# FPGA.net
KiCad netlist of a schematic drawn in Altium Designer
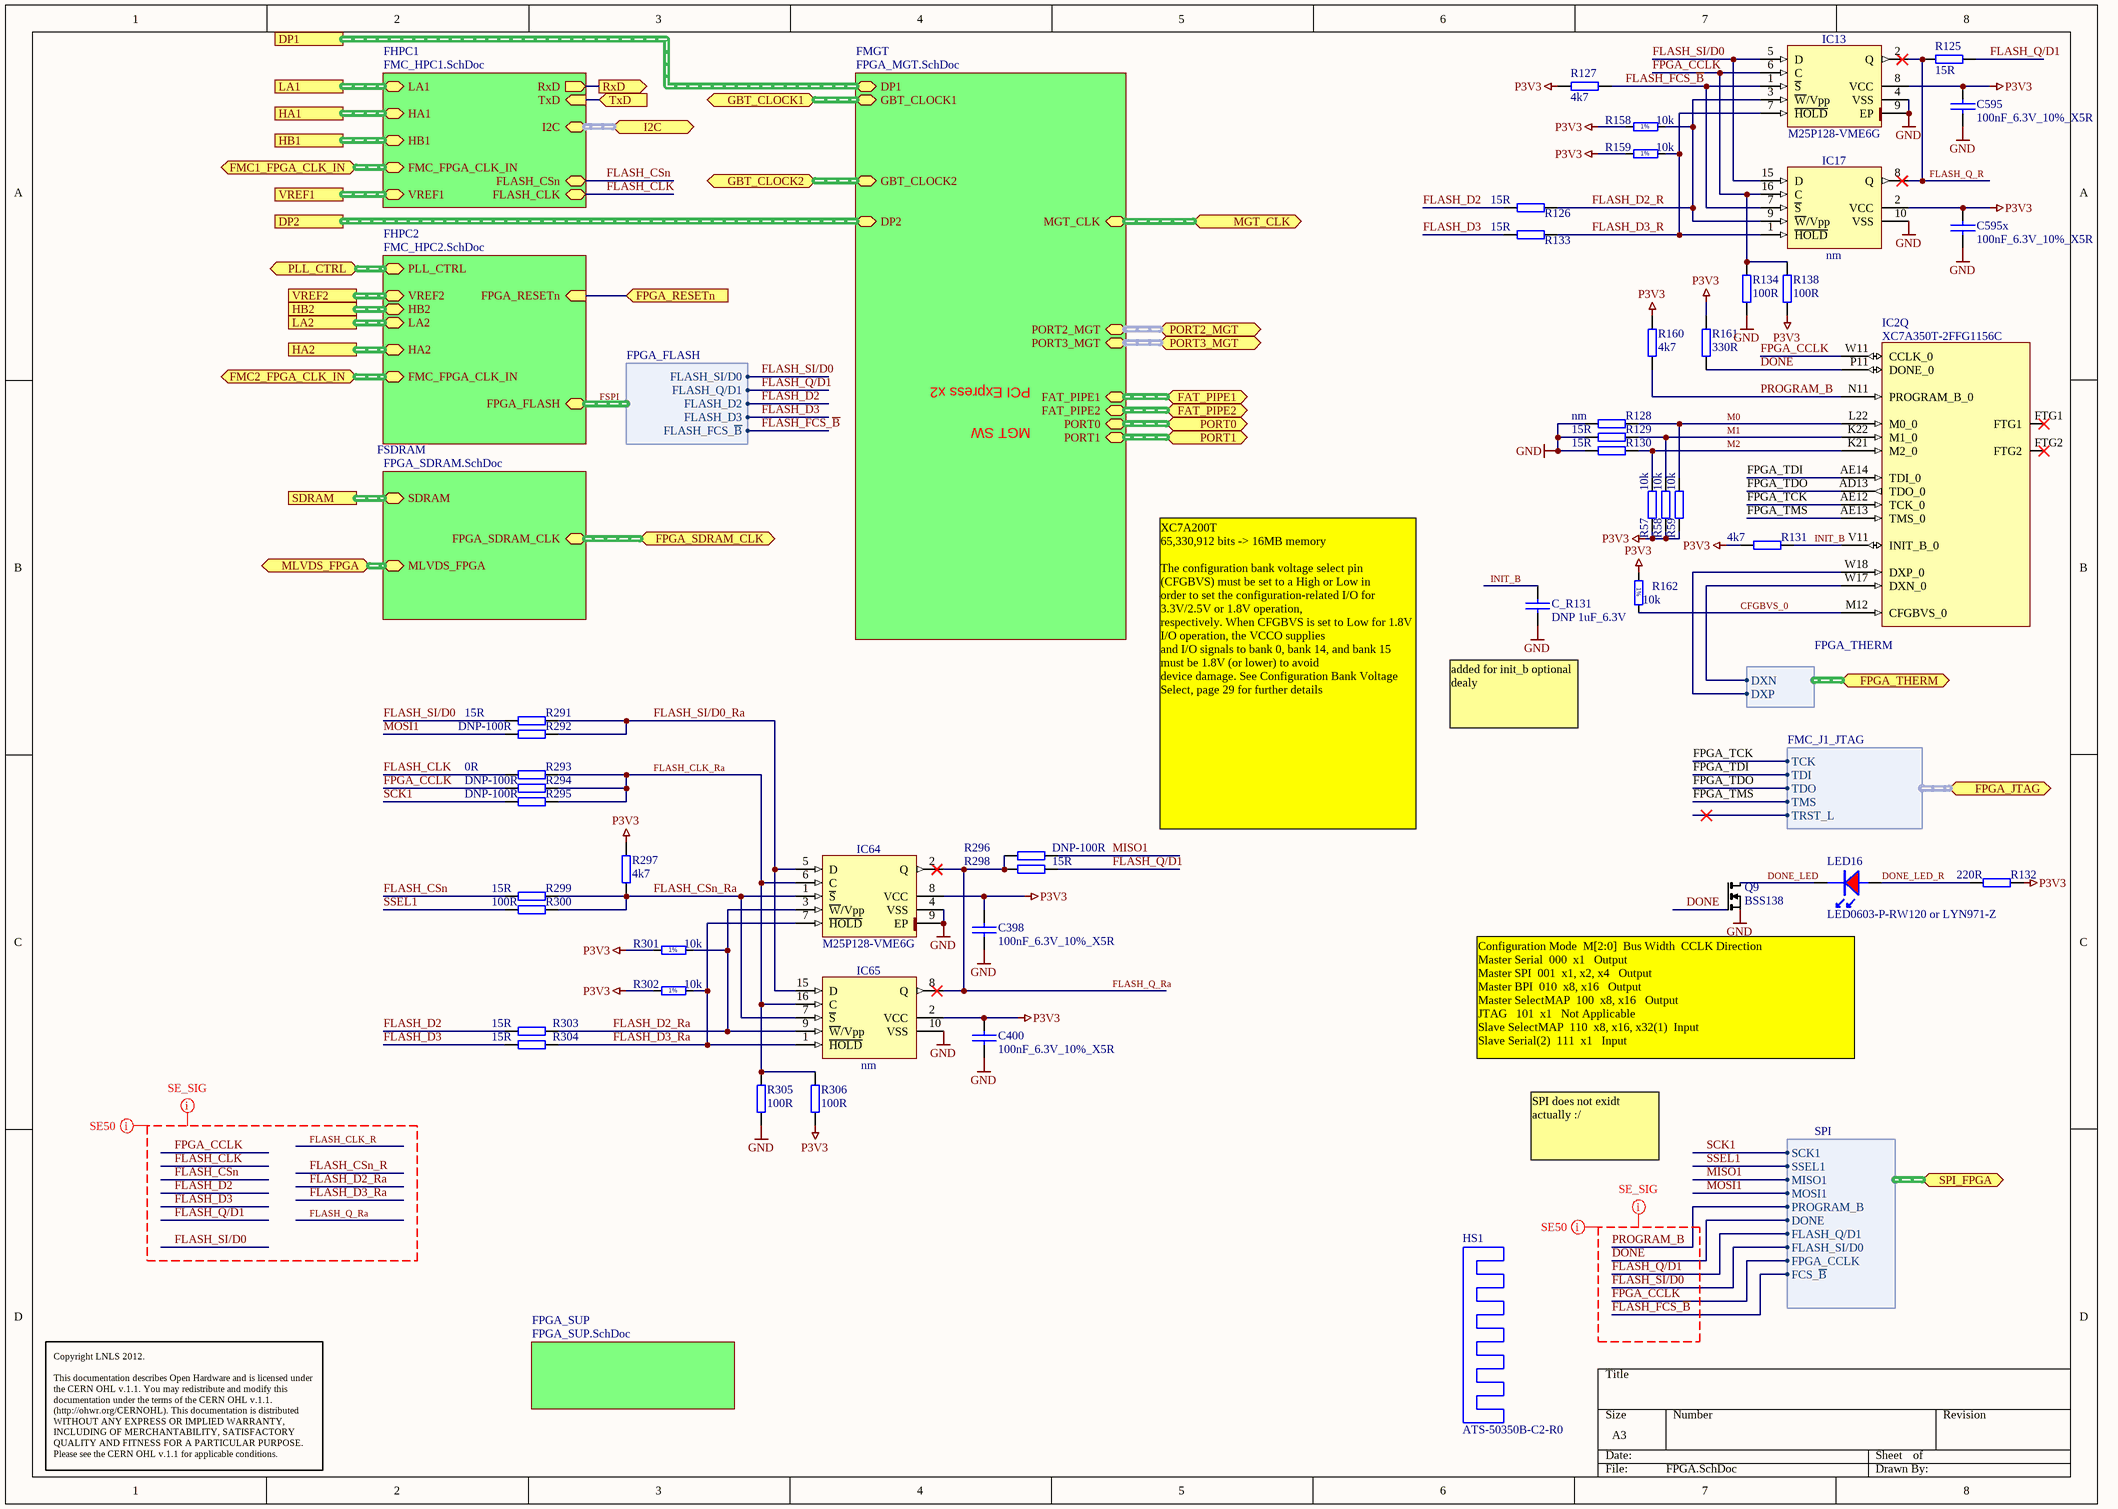
[diagram p0: FPGA.SchDoc]

(export (version "E")
  (design (tool "Eeschema 10.0.6"))
  (components
    (comp (ref "C398")
      (value "100nF_6.3V_10%_X5R")
      (footprint "0201C")
      (description "Capacitor SMD")
      (libsource (lib "LIBRARY_SCH") (part "CAP_SMD_0201"))
    )
    (comp (ref "C400")
      (value "100nF_6.3V_10%_X5R")
      (footprint "0201C")
      (description "Capacitor SMD")
      (libsource (lib "LIBRARY_SCH") (part "CAP_SMD_0201"))
    )
    (comp (ref "C595")
      (value "100nF_6.3V_10%_X5R")
      (footprint "0201C")
      (description "Capacitor SMD")
      (libsource (lib "LIBRARY_SCH") (part "CAP_SMD_0201"))
    )
    (comp (ref "C595x")
      (value "100nF_6.3V_10%_X5R")
      (footprint "0201C")
      (description "Capacitor SMD")
      (libsource (lib "LIBRARY_SCH") (part "CAP_SMD_0201"))
    )
    (comp (ref "C_R131")
      (value "DNP 1uF_6.3V")
      (footprint "0603C")
      (description "Capacitor SMD")
      (libsource (lib "LIBRARY_SCH") (part "CAP_SMD_0603"))
    )
    (comp (ref "HS1")
      (value "ATS-50350B-C2-R0")
      (footprint "HEAT_SINK_ATS-50350B-C2-R0")
      (description "Heat sink BGA 35x35(44.9)mm")
      (libsource (lib "LIBRARY_SCH") (part "HEAT_SINK_ATS-50350B-C2-R0"))
    )
    (comp (ref "IC2")
      (value "XC7A350T-2FFG1156C")
      (footprint "BGA1156C100P34X34_3500X3500X335")
      (description "Artix-6 FPGA, 16 GTPs, 600 User I/Os, 1156-Pin BGA, Speed Grade 2, Commercial Grade, Pb-Free")
      (fields (field (name "MANUFACTURER") "XILINX") (field (name "AUTHOR") "CERN DEM JLC"))
      (libsource (lib "AMC_FMC_Carrier") (part "XC7A350T-2FFG1156C"))
    )
    (comp (ref "IC13")
      (value "M25P128-VME6G")
      (footprint "PSON127P800X600X100-9N-R640X480")
      (description "128 Mbit (Multilevel), low-voltage, Serial Flash memory with 50-MHz SPI bus interface")
      (fields (field (name "MANUFACTURER") "NUMONYX") (field (name "AUTHOR") "CERN DEM JLC"))
      (libsource (lib "ICs And Semiconductors") (part "M25P128-VME"))
    )
    (comp (ref "IC17")
      (value "nm")
      (footprint "SOIC127P1030X265-16N")
      (description "128 Mbit (Multilevel), low-voltage, Serial Flash memory with 50-MHz SPI bus interface")
      (fields
        (field (name "PART NUMBER") "M25P128-VMF6G")
        (field (name "MANUFACTURER") "NUMONYX")
        (field (name "AUTHOR") "CERN DEM JLC")
      )
      (libsource (lib "ICs And Semiconductors") (part "M25P128-VMF"))
    )
    (comp (ref "IC64")
      (value "M25P128-VME6G")
      (footprint "PSON127P800X600X100-9N-R640X480")
      (description "128 Mbit (Multilevel), low-voltage, Serial Flash memory with 50-MHz SPI bus interface")
      (fields (field (name "MANUFACTURER") "NUMONYX") (field (name "AUTHOR") "CERN DEM JLC"))
      (libsource (lib "ICs And Semiconductors") (part "M25P128-VME"))
    )
    (comp (ref "IC65")
      (value "nm")
      (footprint "SOIC127P1030X265-16N")
      (description "128 Mbit (Multilevel), low-voltage, Serial Flash memory with 50-MHz SPI bus interface")
      (fields
        (field (name "PART NUMBER") "M25P128-VMF6G")
        (field (name "MANUFACTURER") "NUMONYX")
        (field (name "AUTHOR") "CERN DEM JLC")
      )
      (libsource (lib "ICs And Semiconductors") (part "M25P128-VMF"))
    )
    (comp (ref "LED16")
      (value "LED0603-P-RW120 or LYN971-Z")
      (footprint "led_0603R")
      (description "LED 0603 red")
      (libsource (lib "LIBRARY_SCH") (part "LED_0603R"))
    )
    (comp (ref "Q9") (value "BSS138") (footprint "SOT-23") (libsource (lib "LIBRARY_SCH") (part "Q_BSS138")))
    (comp (ref "R57")
      (value "10k")
      (footprint "0402R")
      (description "SMD Resistor")
      (libsource (lib "LIBRARY_SCH") (part "RES_0402"))
    )
    (comp (ref "R58")
      (value "10k")
      (footprint "0402R")
      (description "SMD Resistor")
      (libsource (lib "LIBRARY_SCH") (part "RES_0402"))
    )
    (comp (ref "R59")
      (value "10k")
      (footprint "0402R")
      (description "SMD Resistor")
      (libsource (lib "LIBRARY_SCH") (part "RES_0402"))
    )
    (comp (ref "R125")
      (value "15R")
      (footprint "0402R")
      (description "SMD Resistor")
      (libsource (lib "LIBRARY_SCH") (part "RES_0402"))
    )
    (comp (ref "R126")
      (value "15R")
      (footprint "0402R")
      (description "SMD Resistor")
      (libsource (lib "LIBRARY_SCH") (part "RES_0402"))
    )
    (comp (ref "R127")
      (value "4k7")
      (footprint "0402R")
      (description "SMD Resistor")
      (libsource (lib "LIBRARY_SCH") (part "RES_0402"))
    )
    (comp (ref "R128")
      (value "nm")
      (footprint "0402R")
      (description "SMD Resistor")
      (libsource (lib "LIBRARY_SCH") (part "RES_0402"))
    )
    (comp (ref "R129")
      (value "15R")
      (footprint "0402R")
      (description "SMD Resistor")
      (libsource (lib "LIBRARY_SCH") (part "RES_0402"))
    )
    (comp (ref "R130")
      (value "15R")
      (footprint "0402R")
      (description "SMD Resistor")
      (libsource (lib "LIBRARY_SCH") (part "RES_0402"))
    )
    (comp (ref "R131")
      (value "4k7")
      (footprint "0402R")
      (description "SMD Resistor")
      (libsource (lib "LIBRARY_SCH") (part "RES_0402"))
    )
    (comp (ref "R132")
      (value "220R")
      (footprint "0402R")
      (description "SMD Resistor")
      (libsource (lib "LIBRARY_SCH") (part "RES_0402"))
    )
    (comp (ref "R133")
      (value "15R")
      (footprint "0402R")
      (description "SMD Resistor")
      (libsource (lib "LIBRARY_SCH") (part "RES_0402"))
    )
    (comp (ref "R134")
      (value "100R")
      (footprint "0402R")
      (description "SMD Resistor")
      (libsource (lib "LIBRARY_SCH") (part "RES_0402"))
    )
    (comp (ref "R138")
      (value "100R")
      (footprint "0402R")
      (description "SMD Resistor")
      (libsource (lib "LIBRARY_SCH") (part "RES_0402"))
    )
    (comp (ref "R158")
      (value "10k")
      (footprint "0402R")
      (description "Resistor - 1%")
      (fields
        (field (name "PART NUMBER") "R0603_10K_1%_0.1W_100PPM")
        (field (name "POWER") "0.1W")
        (field (name "AUTHOR") "CERN DEM JLC")
      )
      (libsource (lib "Resistors") (part "Resistor - 1%"))
    )
    (comp (ref "R159")
      (value "10k")
      (footprint "0402R")
      (description "Resistor - 1%")
      (fields
        (field (name "PART NUMBER") "R0603_10K_1%_0.1W_100PPM")
        (field (name "POWER") "0.1W")
        (field (name "AUTHOR") "CERN DEM JLC")
      )
      (libsource (lib "Resistors") (part "Resistor - 1%"))
    )
    (comp (ref "R160")
      (value "4k7")
      (footprint "0402R")
      (description "SMD Resistor")
      (libsource (lib "LIBRARY_SCH") (part "RES_0402"))
    )
    (comp (ref "R161")
      (value "330R")
      (footprint "0402R")
      (description "SMD Resistor")
      (libsource (lib "LIBRARY_SCH") (part "RES_0402"))
    )
    (comp (ref "R162")
      (value "10k")
      (footprint "0402R")
      (description "Resistor - 1%")
      (fields
        (field (name "PART NUMBER") "R0603_10K_1%_0.1W_100PPM")
        (field (name "POWER") "0.1W")
        (field (name "AUTHOR") "CERN DEM JLC")
      )
      (libsource (lib "Resistors") (part "Resistor - 1%"))
    )
    (comp (ref "R291")
      (value "15R")
      (footprint "0402R")
      (description "SMD Resistor")
      (libsource (lib "LIBRARY_SCH") (part "RES_0402"))
    )
    (comp (ref "R292")
      (value "DNP-100R")
      (footprint "0402R")
      (description "SMD Resistor")
      (libsource (lib "LIBRARY_SCH") (part "RES_0402"))
    )
    (comp (ref "R293")
      (value "0R")
      (footprint "0402R")
      (description "SMD Resistor")
      (libsource (lib "LIBRARY_SCH") (part "RES_0402"))
    )
    (comp (ref "R294")
      (value "DNP-100R")
      (footprint "0402R")
      (description "SMD Resistor")
      (libsource (lib "LIBRARY_SCH") (part "RES_0402"))
    )
    (comp (ref "R295")
      (value "DNP-100R")
      (footprint "0402R")
      (description "SMD Resistor")
      (libsource (lib "LIBRARY_SCH") (part "RES_0402"))
    )
    (comp (ref "R296")
      (value "DNP-100R")
      (footprint "0402R")
      (description "SMD Resistor")
      (libsource (lib "LIBRARY_SCH") (part "RES_0402"))
    )
    (comp (ref "R297")
      (value "4k7")
      (footprint "0402R")
      (description "SMD Resistor")
      (libsource (lib "LIBRARY_SCH") (part "RES_0402"))
    )
    (comp (ref "R298")
      (value "15R")
      (footprint "0402R")
      (description "SMD Resistor")
      (libsource (lib "LIBRARY_SCH") (part "RES_0402"))
    )
    (comp (ref "R299")
      (value "15R")
      (footprint "0402R")
      (description "SMD Resistor")
      (libsource (lib "LIBRARY_SCH") (part "RES_0402"))
    )
    (comp (ref "R300")
      (value "100R")
      (footprint "0402R")
      (description "SMD Resistor")
      (libsource (lib "LIBRARY_SCH") (part "RES_0402"))
    )
    (comp (ref "R301")
      (value "10k")
      (footprint "0402R")
      (description "Resistor - 1%")
      (fields
        (field (name "PART NUMBER") "R0603_10K_1%_0.1W_100PPM")
        (field (name "POWER") "0.1W")
        (field (name "AUTHOR") "CERN DEM JLC")
      )
      (libsource (lib "Resistors") (part "Resistor - 1%"))
    )
    (comp (ref "R302")
      (value "10k")
      (footprint "0402R")
      (description "Resistor - 1%")
      (fields
        (field (name "PART NUMBER") "R0603_10K_1%_0.1W_100PPM")
        (field (name "POWER") "0.1W")
        (field (name "AUTHOR") "CERN DEM JLC")
      )
      (libsource (lib "Resistors") (part "Resistor - 1%"))
    )
    (comp (ref "R303")
      (value "15R")
      (footprint "0402R")
      (description "SMD Resistor")
      (libsource (lib "LIBRARY_SCH") (part "RES_0402"))
    )
    (comp (ref "R304")
      (value "15R")
      (footprint "0402R")
      (description "SMD Resistor")
      (libsource (lib "LIBRARY_SCH") (part "RES_0402"))
    )
    (comp (ref "R305")
      (value "100R")
      (footprint "0402R")
      (description "SMD Resistor")
      (libsource (lib "LIBRARY_SCH") (part "RES_0402"))
    )
    (comp (ref "R306")
      (value "100R")
      (footprint "0402R")
      (description "SMD Resistor")
      (libsource (lib "LIBRARY_SCH") (part "RES_0402"))
    )
  )
  (nets
    (net (code "12") (name "/CFGBVS_0") (class "Default")
      (node (ref "IC2") (pin "M12") (pinfunction "CFGBVS_0_M12") (pintype "input"))
      (node (ref "R162") (pin "2") (pinfunction "2_2") (pintype "passive"))
    )
    (net (code "13") (name "/DONE") (class "Default")
      (node (ref "IC2") (pin "P11") (pinfunction "DONE_0_P11") (pintype "bidirectional"))
      (node (ref "Q9") (pin "1") (pinfunction "G_1") (pintype "input"))
      (node (ref "R161") (pin "1") (pinfunction "1_1") (pintype "passive"))
    )
    (net (code "14") (name "/DONE_LED") (class "Default")
      (node (ref "LED16") (pin "K") (pinfunction "K_K") (pintype "passive"))
      (node (ref "Q9") (pin "3") (pinfunction "D_3") (pintype "passive"))
    )
    (net (code "15") (name "/DONE_LED_R") (class "Default")
      (node (ref "LED16") (pin "A") (pinfunction "A_A") (pintype "passive"))
      (node (ref "R132") (pin "1") (pinfunction "1_1") (pintype "passive"))
    )
    (net (code "18") (name "/DXN") (class "Default")
      (node (ref "IC2") (pin "W17") (pinfunction "DXN_0_W17") (pintype "input"))
    )
    (net (code "19") (name "/DXP") (class "Default")
      (node (ref "IC2") (pin "W18") (pinfunction "DXP_0_W18") (pintype "input"))
    )
    (net (code "24") (name "/FLASH_CLK") (class "Default")
      (node (ref "R293") (pin "1") (pinfunction "1_1") (pintype "passive"))
    )
    (net (code "26") (name "/FLASH_CLK_Ra") (class "Default")
      (node (ref "IC64") (pin "6") (pinfunction "C_6") (pintype "input"))
      (node (ref "IC65") (pin "16") (pinfunction "C_16") (pintype "input"))
      (node (ref "R293") (pin "2") (pinfunction "2_2") (pintype "passive"))
      (node (ref "R294") (pin "2") (pinfunction "2_2") (pintype "passive"))
      (node (ref "R295") (pin "2") (pinfunction "2_2") (pintype "passive"))
      (node (ref "R305") (pin "2") (pinfunction "2_2") (pintype "passive"))
      (node (ref "R306") (pin "2") (pinfunction "2_2") (pintype "passive"))
    )
    (net (code "27") (name "/FLASH_CSn") (class "Default")
      (node (ref "R299") (pin "1") (pinfunction "1_1") (pintype "passive"))
    )
    (net (code "29") (name "/FLASH_CSn_Ra") (class "Default")
      (node (ref "IC64") (pin "1") (pinfunction "~{S}_1") (pintype "input"))
      (node (ref "IC65") (pin "7") (pinfunction "~{S}_7") (pintype "input"))
      (node (ref "R297") (pin "1") (pinfunction "1_1") (pintype "passive"))
      (node (ref "R299") (pin "2") (pinfunction "2_2") (pintype "passive"))
      (node (ref "R300") (pin "2") (pinfunction "2_2") (pintype "passive"))
    )
    (net (code "30") (name "/FLASH_D2") (class "Default")
      (node (ref "R126") (pin "1") (pinfunction "1_1") (pintype "passive"))
      (node (ref "R303") (pin "1") (pinfunction "1_1") (pintype "passive"))
    )
    (net (code "31") (name "/FLASH_D2_R") (class "Default")
      (node (ref "IC13") (pin "3") (pinfunction "~{W}/Vpp_3") (pintype "input"))
      (node (ref "IC17") (pin "9") (pinfunction "~{W}/Vpp_9") (pintype "input"))
      (node (ref "R126") (pin "2") (pinfunction "2_2") (pintype "passive"))
      (node (ref "R158") (pin "2") (pinfunction "2_2") (pintype "passive"))
    )
    (net (code "32") (name "/FLASH_D2_Ra") (class "Default")
      (node (ref "IC64") (pin "3") (pinfunction "~{W}/Vpp_3") (pintype "input"))
      (node (ref "IC65") (pin "9") (pinfunction "~{W}/Vpp_9") (pintype "input"))
      (node (ref "R301") (pin "2") (pinfunction "2_2") (pintype "passive"))
      (node (ref "R303") (pin "2") (pinfunction "2_2") (pintype "passive"))
    )
    (net (code "33") (name "/FLASH_D3") (class "Default")
      (node (ref "R133") (pin "1") (pinfunction "1_1") (pintype "passive"))
      (node (ref "R304") (pin "1") (pinfunction "1_1") (pintype "passive"))
    )
    (net (code "34") (name "/FLASH_D3_R") (class "Default")
      (node (ref "IC13") (pin "7") (pinfunction "~{HOLD}_7") (pintype "input"))
      (node (ref "IC17") (pin "1") (pinfunction "~{HOLD}_1") (pintype "input"))
      (node (ref "R133") (pin "2") (pinfunction "2_2") (pintype "passive"))
      (node (ref "R159") (pin "2") (pinfunction "2_2") (pintype "passive"))
    )
    (net (code "35") (name "/FLASH_D3_Ra") (class "Default")
      (node (ref "IC64") (pin "7") (pinfunction "~{HOLD}_7") (pintype "input"))
      (node (ref "IC65") (pin "1") (pinfunction "~{HOLD}_1") (pintype "input"))
      (node (ref "R302") (pin "2") (pinfunction "2_2") (pintype "passive"))
      (node (ref "R304") (pin "2") (pinfunction "2_2") (pintype "passive"))
    )
    (net (code "36") (name "/FLASH_FCS_~{B}") (class "Default")
      (node (ref "IC13") (pin "1") (pinfunction "~{S}_1") (pintype "input"))
      (node (ref "IC17") (pin "7") (pinfunction "~{S}_7") (pintype "input"))
      (node (ref "R127") (pin "1") (pinfunction "1_1") (pintype "passive"))
    )
    (net (code "37") (name "/FLASH_Q_R") (class "Default")
      (node (ref "IC13") (pin "2") (pinfunction "Q_2") (pintype "output"))
      (node (ref "IC17") (pin "8") (pinfunction "Q_8") (pintype "output"))
      (node (ref "R125") (pin "1") (pinfunction "1_1") (pintype "passive"))
    )
    (net (code "38") (name "/FLASH_Q_Ra") (class "Default")
      (node (ref "IC64") (pin "2") (pinfunction "Q_2") (pintype "output"))
      (node (ref "IC65") (pin "8") (pinfunction "Q_8") (pintype "output"))
      (node (ref "R296") (pin "1") (pinfunction "1_1") (pintype "passive"))
      (node (ref "R298") (pin "1") (pinfunction "1_1") (pintype "passive"))
    )
    (net (code "39") (name "/FLASH_Q{slash}D1") (class "Default")
      (node (ref "R125") (pin "2") (pinfunction "2_2") (pintype "passive"))
      (node (ref "R298") (pin "2") (pinfunction "2_2") (pintype "passive"))
    )
    (net (code "40") (name "/FLASH_SI{slash}D0") (class "Default")
      (node (ref "IC13") (pin "5") (pinfunction "D_5") (pintype "input"))
      (node (ref "IC17") (pin "15") (pinfunction "D_15") (pintype "input"))
      (node (ref "R291") (pin "1") (pinfunction "1_1") (pintype "passive"))
    )
    (net (code "41") (name "/FLASH_SI{slash}D0_Ra") (class "Default")
      (node (ref "IC64") (pin "5") (pinfunction "D_5") (pintype "input"))
      (node (ref "IC65") (pin "15") (pinfunction "D_15") (pintype "input"))
      (node (ref "R291") (pin "2") (pinfunction "2_2") (pintype "passive"))
      (node (ref "R292") (pin "2") (pinfunction "2_2") (pintype "passive"))
    )
    (net (code "44") (name "/FPGA_CCLK") (class "Default")
      (node (ref "IC13") (pin "6") (pinfunction "C_6") (pintype "input"))
      (node (ref "IC17") (pin "16") (pinfunction "C_16") (pintype "input"))
      (node (ref "IC2") (pin "W11") (pinfunction "CCLK_0_W11") (pintype "bidirectional"))
      (node (ref "R134") (pin "2") (pinfunction "2_2") (pintype "passive"))
      (node (ref "R138") (pin "2") (pinfunction "2_2") (pintype "passive"))
      (node (ref "R294") (pin "1") (pinfunction "1_1") (pintype "passive"))
    )
    (net (code "48") (name "/FPGA_TCK") (class "Default")
      (node (ref "IC2") (pin "AE12") (pinfunction "TCK_0_AE12") (pintype "input"))
    )
    (net (code "49") (name "/FPGA_TDI") (class "Default")
      (node (ref "IC2") (pin "AE14") (pinfunction "TDI_0_AE14") (pintype "input"))
    )
    (net (code "50") (name "/FPGA_TDO") (class "Default")
      (node (ref "IC2") (pin "AD13") (pinfunction "TDO_0_AD13") (pintype "output"))
    )
    (net (code "51") (name "/FPGA_TMS") (class "Default")
      (node (ref "IC2") (pin "AE13") (pinfunction "TMS_0_AE13") (pintype "input"))
    )
    (net (code "60") (name "/INIT_B") (class "Default")
      (node (ref "C_R131") (pin "2") (pinfunction "2_2") (pintype "passive"))
      (node (ref "IC2") (pin "V11") (pinfunction "INIT_B_0_V11") (pintype "bidirectional"))
      (node (ref "R131") (pin "2") (pinfunction "2_2") (pintype "passive"))
    )
    (net (code "63") (name "/M0") (class "Default")
      (node (ref "IC2") (pin "L22") (pinfunction "M0_0_L22") (pintype "input"))
      (node (ref "R128") (pin "2") (pinfunction "2_2") (pintype "passive"))
      (node (ref "R59") (pin "2") (pinfunction "2_2") (pintype "passive"))
    )
    (net (code "64") (name "/M1") (class "Default")
      (node (ref "IC2") (pin "K22") (pinfunction "M1_0_K22") (pintype "input"))
      (node (ref "R129") (pin "2") (pinfunction "2_2") (pintype "passive"))
      (node (ref "R58") (pin "2") (pinfunction "2_2") (pintype "passive"))
    )
    (net (code "65") (name "/M2") (class "Default")
      (node (ref "IC2") (pin "K21") (pinfunction "M2_0_K21") (pintype "input"))
      (node (ref "R130") (pin "2") (pinfunction "2_2") (pintype "passive"))
      (node (ref "R57") (pin "2") (pinfunction "2_2") (pintype "passive"))
    )
    (net (code "68") (name "/MISO1") (class "Default")
      (node (ref "R296") (pin "2") (pinfunction "2_2") (pintype "passive"))
    )
    (net (code "70") (name "/MOSI1") (class "Default")
      (node (ref "R292") (pin "1") (pinfunction "1_1") (pintype "passive"))
    )
    (net (code "78") (name "/PROGRAM_B") (class "Default")
      (node (ref "IC2") (pin "N11") (pinfunction "PROGRAM_B_0_N11") (pintype "input"))
      (node (ref "R160") (pin "1") (pinfunction "1_1") (pintype "passive"))
    )
    (net (code "80") (name "/SCK1") (class "Default")
      (node (ref "R295") (pin "1") (pinfunction "1_1") (pintype "passive"))
    )
    (net (code "82") (name "/SSEL1") (class "Default")
      (node (ref "R300") (pin "1") (pinfunction "1_1") (pintype "passive"))
    )
    (net (code "90") (name "GND") (class "Default")
      (node (ref "C398") (pin "2") (pinfunction "2_2") (pintype "passive"))
      (node (ref "C400") (pin "2") (pinfunction "2_2") (pintype "passive"))
      (node (ref "C595") (pin "2") (pinfunction "2_2") (pintype "passive"))
      (node (ref "C595x") (pin "2") (pinfunction "2_2") (pintype "passive"))
      (node (ref "C_R131") (pin "1") (pinfunction "1_1") (pintype "passive"))
      (node (ref "IC13") (pin "4") (pinfunction "VSS_4") (pintype "power_in"))
      (node (ref "IC13") (pin "9") (pinfunction "EP_9") (pintype "power_in"))
      (node (ref "IC17") (pin "10") (pinfunction "VSS_10") (pintype "power_in"))
      (node (ref "IC64") (pin "4") (pinfunction "VSS_4") (pintype "power_in"))
      (node (ref "IC64") (pin "9") (pinfunction "EP_9") (pintype "power_in"))
      (node (ref "IC65") (pin "10") (pinfunction "VSS_10") (pintype "power_in"))
      (node (ref "Q9") (pin "2") (pinfunction "S_2") (pintype "passive"))
      (node (ref "R128") (pin "1") (pinfunction "1_1") (pintype "passive"))
      (node (ref "R129") (pin "1") (pinfunction "1_1") (pintype "passive"))
      (node (ref "R130") (pin "1") (pinfunction "1_1") (pintype "passive"))
      (node (ref "R134") (pin "1") (pinfunction "1_1") (pintype "passive"))
      (node (ref "R305") (pin "1") (pinfunction "1_1") (pintype "passive"))
    )
    (net (code "91") (name "P3V3") (class "Default")
      (node (ref "C398") (pin "1") (pinfunction "1_1") (pintype "passive"))
      (node (ref "C400") (pin "1") (pinfunction "1_1") (pintype "passive"))
      (node (ref "C595") (pin "1") (pinfunction "1_1") (pintype "passive"))
      (node (ref "C595x") (pin "1") (pinfunction "1_1") (pintype "passive"))
      (node (ref "IC13") (pin "8") (pinfunction "VCC_8") (pintype "power_in"))
      (node (ref "IC17") (pin "2") (pinfunction "VCC_2") (pintype "power_in"))
      (node (ref "IC64") (pin "8") (pinfunction "VCC_8") (pintype "power_in"))
      (node (ref "IC65") (pin "2") (pinfunction "VCC_2") (pintype "power_in"))
      (node (ref "R127") (pin "2") (pinfunction "2_2") (pintype "passive"))
      (node (ref "R131") (pin "1") (pinfunction "1_1") (pintype "passive"))
      (node (ref "R132") (pin "2") (pinfunction "2_2") (pintype "passive"))
      (node (ref "R138") (pin "1") (pinfunction "1_1") (pintype "passive"))
      (node (ref "R158") (pin "1") (pinfunction "1_1") (pintype "passive"))
      (node (ref "R159") (pin "1") (pinfunction "1_1") (pintype "passive"))
      (node (ref "R160") (pin "2") (pinfunction "2_2") (pintype "passive"))
      (node (ref "R161") (pin "2") (pinfunction "2_2") (pintype "passive"))
      (node (ref "R162") (pin "1") (pinfunction "1_1") (pintype "passive"))
      (node (ref "R297") (pin "2") (pinfunction "2_2") (pintype "passive"))
      (node (ref "R301") (pin "1") (pinfunction "1_1") (pintype "passive"))
      (node (ref "R302") (pin "1") (pinfunction "1_1") (pintype "passive"))
      (node (ref "R306") (pin "1") (pinfunction "1_1") (pintype "passive"))
      (node (ref "R57") (pin "1") (pinfunction "1_1") (pintype "passive"))
      (node (ref "R58") (pin "1") (pinfunction "1_1") (pintype "passive"))
      (node (ref "R59") (pin "1") (pinfunction "1_1") (pintype "passive"))
    )
    (net (code "92") (name "unconnected-(IC2-PadFTG1)") (class "Default")
      (node (ref "IC2") (pin "FTG1") (pinfunction "FTG1_FTG1") (pintype "passive+no_connect"))
    )
    (net (code "93") (name "unconnected-(IC2-PadFTG2)") (class "Default")
      (node (ref "IC2") (pin "FTG2") (pinfunction "FTG2_FTG2") (pintype "passive+no_connect"))
    )
  )
)
